# LOINA.net
KiCad netlist of a schematic drawn in Altium Designer
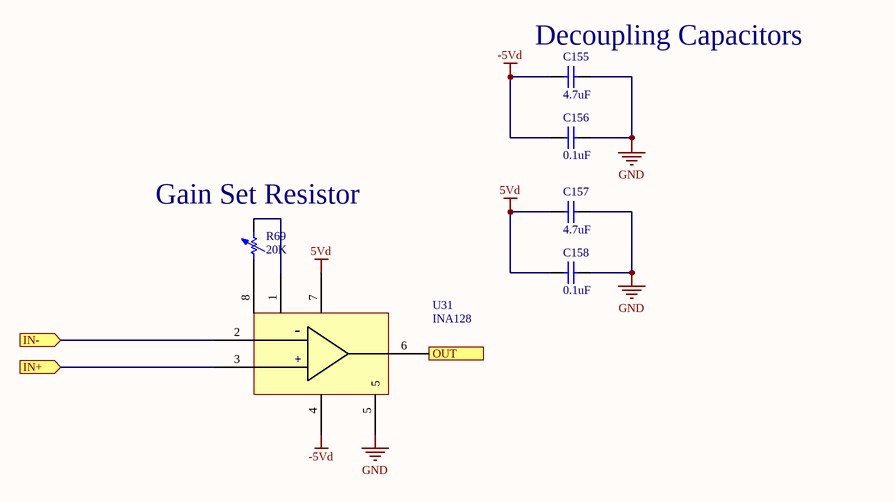
[diagram p0: LOINA.SchDoc]

(export (version "E")
  (design (tool "Eeschema 10.0.6"))
  (components
    (comp (ref "C155")
      (value "4.7uF")
      (footprint "0402_Cap")
      (description "Capacitor, 4.7uF, 0805")
      (libsource (lib "Arturo_Approved") (part "CL21A475KAQNNNE"))
    )
    (comp (ref "C156")
      (value "0.1uF")
      (footprint "0402_Cap")
      (description "Capacitor, 0.1uF, 0805")
      (libsource (lib "Arturo_Approved") (part "CL21B104KACNNNC"))
    )
    (comp (ref "C157")
      (value "4.7uF")
      (footprint "0402_Cap")
      (description "Capacitor, 4.7uF, 0805")
      (libsource (lib "Arturo_Approved") (part "CL21A475KAQNNNE"))
    )
    (comp (ref "C158")
      (value "0.1uF")
      (footprint "0402_Cap")
      (description "Capacitor, 0.1uF, 0805")
      (libsource (lib "Arturo_Approved") (part "CL21B104KACNNNC"))
    )
    (comp (ref "R69")
      (value "20K")
      (footprint "TRIMRES")
      (description "Variable resistor 1k")
      (libsource (lib "Arturo_Approved") (part "PV36W102C01B00_RES"))
    )
    (comp (ref "U31")
      (value "INA128")
      (footprint "SOIC_8")
      (description "Instrumentation Amp, Generic")
      (libsource (lib "Arturo_Approved") (part "INA128UA/2K5"))
    )
  )
  (nets
    (net (code "1") (name "-5Vd") (class "Default")
      (node (ref "C155") (pin "1") (pinfunction "1_1") (pintype "passive"))
      (node (ref "C156") (pin "1") (pinfunction "1_1") (pintype "passive"))
      (node (ref "U31") (pin "4") (pintype "passive"))
    )
    (net (code "2") (name "/IN+") (class "Default") (node (ref "U31") (pin "3") (pintype "passive")))
    (net (code "3") (name "/IN-") (class "Default") (node (ref "U31") (pin "2") (pintype "passive")))
    (net (code "4") (name "/OUT") (class "Default") (node (ref "U31") (pin "6") (pintype "passive")))
    (net (code "5") (name "5Vd") (class "Default")
      (node (ref "C157") (pin "1") (pinfunction "1_1") (pintype "passive"))
      (node (ref "C158") (pin "1") (pinfunction "1_1") (pintype "passive"))
      (node (ref "U31") (pin "7") (pintype "passive"))
    )
    (net (code "6") (name "GND") (class "Default")
      (node (ref "C155") (pin "2") (pinfunction "2_2") (pintype "passive"))
      (node (ref "C156") (pin "2") (pinfunction "2_2") (pintype "passive"))
      (node (ref "C157") (pin "2") (pinfunction "2_2") (pintype "passive"))
      (node (ref "C158") (pin "2") (pinfunction "2_2") (pintype "passive"))
      (node (ref "U31") (pin "5") (pinfunction "5_5") (pintype "passive"))
    )
    (net (code "7") (name "Net-(R69-Pad1)") (class "Default")
      (node (ref "R69") (pin "1") (pinfunction "1_1") (pintype "passive"))
      (node (ref "U31") (pin "8") (pinfunction "Gain_8") (pintype "passive"))
    )
    (net (code "8") (name "Net-(R69-Pad2)") (class "Default")
      (node (ref "R69") (pin "2") (pinfunction "2_2") (pintype "passive"))
      (node (ref "U31") (pin "1") (pinfunction "Gain_1") (pintype "passive"))
    )
  )
)
